# CAN.net
KiCad netlist of a schematic drawn in Altium Designer
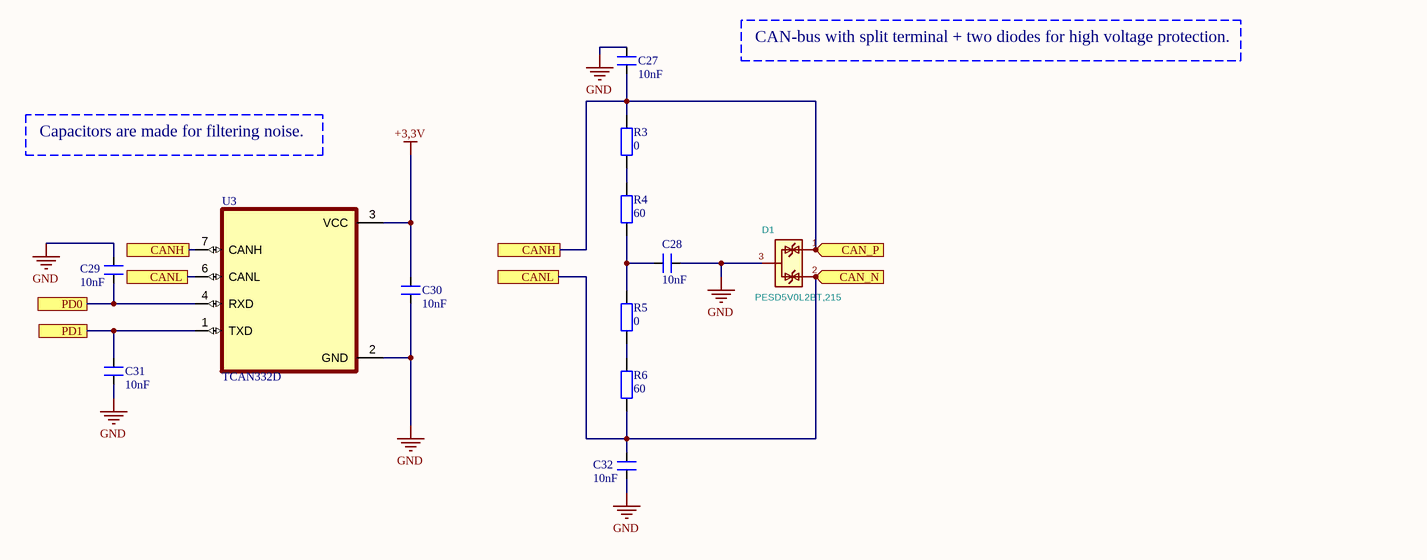
[diagram p0: CAN.SchDoc]

(export (version "E")
  (design (tool "Eeschema 10.0.6"))
  (components
    (comp (ref "C27")
      (value "10nF")
      (footprint "FP-C0603C-CF-IPC_A")
      (description "Capacitor (Semiconductor SIM Model)")
      (fields (field (name "PUBLISHER") "Altium Limited"))
      (libsource (lib "LIBRARY") (part "CN-SEMI-DIP"))
    )
    (comp (ref "C28")
      (value "10nF")
      (footprint "FP-C0603C-CF-IPC_A")
      (description "Capacitor (Semiconductor SIM Model)")
      (fields (field (name "PUBLISHER") "Altium Limited"))
      (libsource (lib "LIBRARY") (part "CN-SEMI-DIP"))
    )
    (comp (ref "C29")
      (value "10nF")
      (footprint "FP-C0603C-CF-IPC_A")
      (description "Capacitor (Semiconductor SIM Model)")
      (fields (field (name "PUBLISHER") "Altium Limited"))
      (libsource (lib "LIBRARY") (part "CN-SEMI-DIP"))
    )
    (comp (ref "C30")
      (value "10nF")
      (footprint "FP-C0603C-CF-IPC_A")
      (description "Capacitor (Semiconductor SIM Model)")
      (fields (field (name "PUBLISHER") "Altium Limited"))
      (libsource (lib "LIBRARY") (part "CN-SEMI-DIP"))
    )
    (comp (ref "C31")
      (value "10nF")
      (footprint "FP-C0603C-CF-IPC_A")
      (description "Capacitor (Semiconductor SIM Model)")
      (fields (field (name "PUBLISHER") "Altium Limited"))
      (libsource (lib "LIBRARY") (part "CN-SEMI-DIP"))
    )
    (comp (ref "C32")
      (value "10nF")
      (footprint "FP-C0603C-CF-IPC_A")
      (description "Capacitor (Semiconductor SIM Model)")
      (fields (field (name "PUBLISHER") "Altium Limited"))
      (libsource (lib "LIBRARY") (part "CN-SEMI-DIP"))
    )
    (comp (ref "D1")
      (value "PESD5V0L2BT,215")
      (footprint "SOT95P230X110-3N")
      (libsource (lib "Power_Protection") (part "NUP2105L"))
    )
    (comp (ref "R3")
      (value "0")
      (footprint "tro smd 0603")
      (description "RES")
      (libsource (lib "AUSB") (part "Tro 0603 1% 10k"))
    )
    (comp (ref "R4")
      (value "60")
      (footprint "tro smd 0603")
      (description "RES")
      (libsource (lib "AUSB") (part "Tro 0603 1% 10k"))
    )
    (comp (ref "R5")
      (value "0")
      (footprint "tro smd 0603")
      (description "RES")
      (libsource (lib "AUSB") (part "Tro 0603 1% 10k"))
    )
    (comp (ref "R6")
      (value "60")
      (footprint "tro smd 0603")
      (description "RES")
      (libsource (lib "AUSB") (part "Tro 0603 1% 10k"))
    )
    (comp (ref "U3")
      (value "TCAN332D")
      (footprint "SOIC127P599X175-8N")
      (description "3.3-V CAN Transceivers")
      (fields (field (name "MF") "Texas Instruments"))
      (libsource (lib "TCAN332D") (part "TCAN332D"))
    )
  )
  (nets
    (net (code "1") (name "+3,3V") (class "Default")
      (node (ref "C30") (pin "2") (pinfunction "2_2") (pintype "passive"))
      (node (ref "U3") (pin "3") (pinfunction "VCC_3") (pintype "power_in"))
    )
    (net (code "2") (name "/CANH") (class "Default")
      (node (ref "C27") (pin "2") (pinfunction "2_2") (pintype "passive"))
      (node (ref "D1") (pin "1") (pinfunction "K_1") (pintype "passive"))
      (node (ref "R3") (pin "2") (pinfunction "2_2") (pintype "passive"))
      (node (ref "U3") (pin "7") (pinfunction "CANH_7") (pintype "bidirectional"))
    )
    (net (code "3") (name "/CANL") (class "Default")
      (node (ref "C32") (pin "2") (pinfunction "2_2") (pintype "passive"))
      (node (ref "D1") (pin "2") (pinfunction "K_2") (pintype "passive"))
      (node (ref "R6") (pin "1") (pinfunction "1_1") (pintype "passive"))
      (node (ref "U3") (pin "6") (pinfunction "CANL_6") (pintype "bidirectional"))
    )
    (net (code "4") (name "/PD0") (class "Default")
      (node (ref "C29") (pin "1") (pinfunction "1_1") (pintype "passive"))
      (node (ref "U3") (pin "4") (pinfunction "RXD_4") (pintype "bidirectional"))
    )
    (net (code "5") (name "/PD1") (class "Default")
      (node (ref "C31") (pin "2") (pinfunction "2_2") (pintype "passive"))
      (node (ref "U3") (pin "1") (pinfunction "TXD_1") (pintype "bidirectional"))
    )
    (net (code "6") (name "GND") (class "Default")
      (node (ref "C27") (pin "1") (pinfunction "1_1") (pintype "passive"))
      (node (ref "C28") (pin "1") (pinfunction "1_1") (pintype "passive"))
      (node (ref "C29") (pin "2") (pinfunction "2_2") (pintype "passive"))
      (node (ref "C30") (pin "1") (pinfunction "1_1") (pintype "passive"))
      (node (ref "C31") (pin "1") (pinfunction "1_1") (pintype "passive"))
      (node (ref "C32") (pin "1") (pinfunction "1_1") (pintype "passive"))
      (node (ref "D1") (pin "3") (pinfunction "A_3") (pintype "passive"))
      (node (ref "U3") (pin "2") (pinfunction "GND_2") (pintype "power_in"))
    )
    (net (code "7") (name "Net-(C28-Pad2)") (class "Default")
      (node (ref "C28") (pin "2") (pinfunction "2_2") (pintype "passive"))
      (node (ref "R4") (pin "1") (pinfunction "1_1") (pintype "passive"))
      (node (ref "R5") (pin "2") (pinfunction "2_2") (pintype "passive"))
    )
    (net (code "8") (name "Net-(R3-Pad1)") (class "Default")
      (node (ref "R3") (pin "1") (pinfunction "1_1") (pintype "passive"))
      (node (ref "R4") (pin "2") (pinfunction "2_2") (pintype "passive"))
    )
    (net (code "9") (name "Net-(R5-Pad1)") (class "Default")
      (node (ref "R5") (pin "1") (pinfunction "1_1") (pintype "passive"))
      (node (ref "R6") (pin "2") (pinfunction "2_2") (pintype "passive"))
    )
  )
)
